# Sheet1.net
KiCad netlist of a schematic drawn in Altium Designer
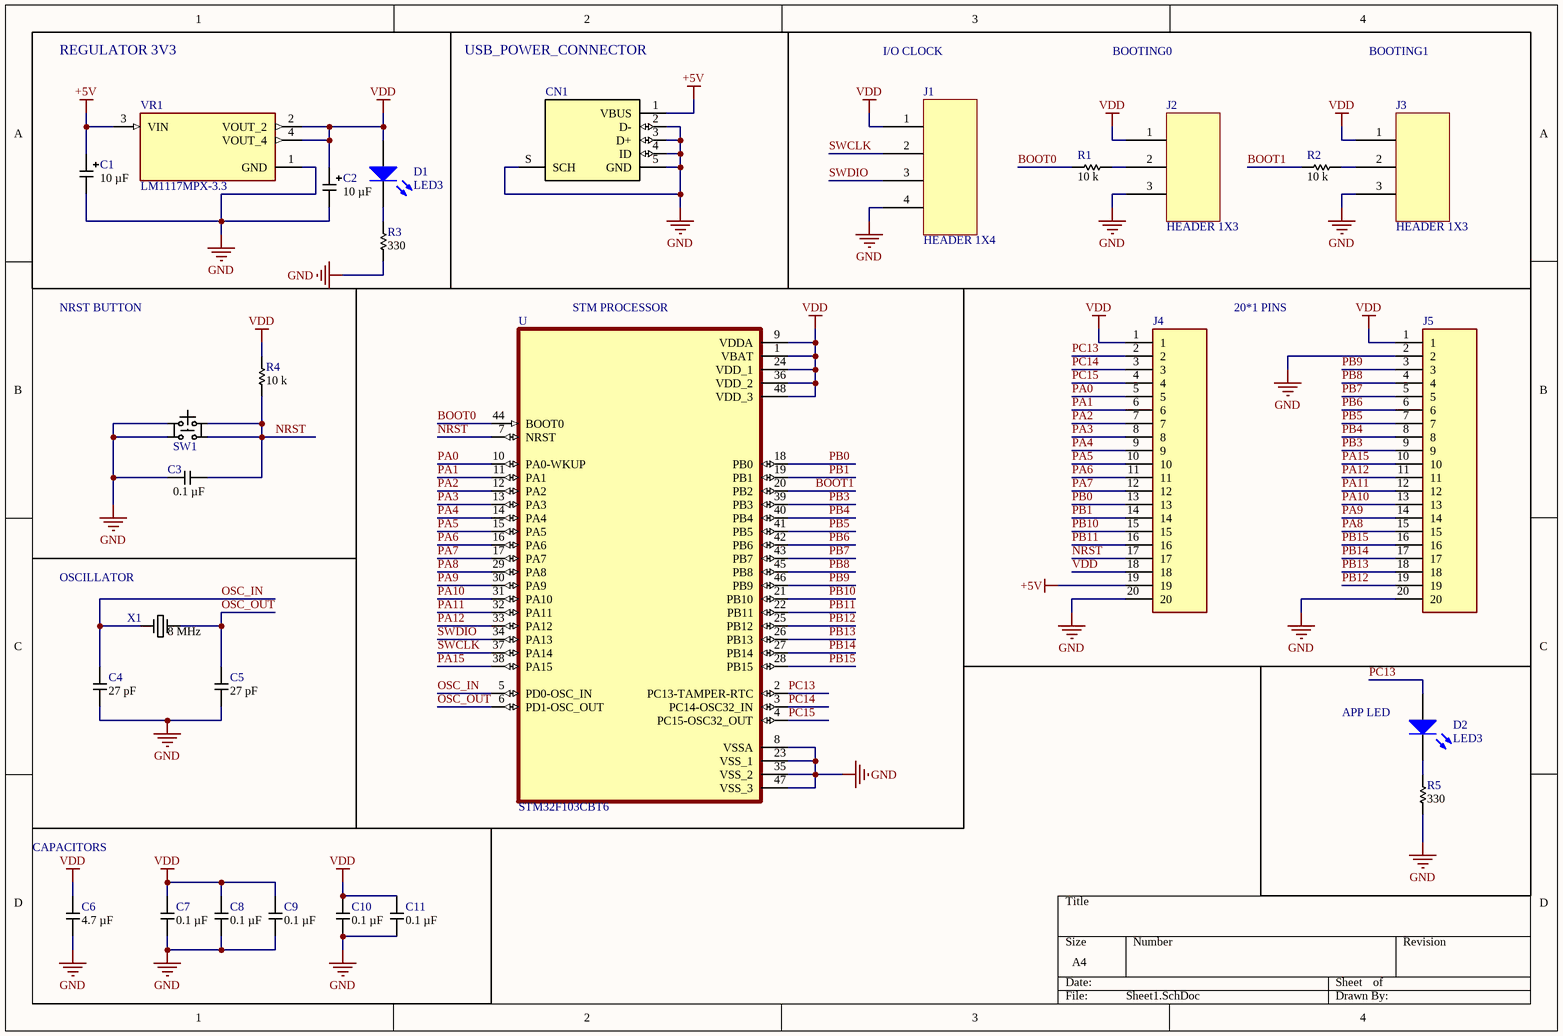
[diagram p0: Sheet1.SchDoc]

(export (version "E")
  (design (tool "Eeschema 10.0.6"))
  (components
    (comp (ref "C1")
      (value "T495B106K025ATE750")
      (footprint "KEMET_CAP_TAN-B")
      (description "CAP TANT 10UF 10% 25V 1411")
      (fields (field (name "CAPACITANCE") "10 µF"))
      (libsource (lib "Tantalum Capacitors") (part "T495B106K025ATE750"))
    )
    (comp (ref "C2")
      (value "T495B106K025ATE750")
      (footprint "KEMET_CAP_TAN-B")
      (description "CAP TANT 10UF 10% 25V 1411")
      (fields (field (name "CAPACITANCE") "10 µF"))
      (libsource (lib "Tantalum Capacitors") (part "T495B106K025ATE750"))
    )
    (comp (ref "C3")
      (value "CL10B104KB8NNNC")
      (footprint "SAMSUNG_CAP_0603_090")
      (description "CAP CER 0.1UF 50V X7R 0603")
      (fields (field (name "CAPACITANCE") "0.1 µF"))
      (libsource (lib "Ceramic Capacitors") (part "CL10B104KB8NNNC"))
    )
    (comp (ref "C4")
      (value "CL21C270JBANNNC")
      (footprint "SAMSUNG_CAP_0805_075")
      (description "CAP CER 27PF 50V C0G/NP0 0805")
      (fields (field (name "CAPACITANCE") "27 pF"))
      (libsource (lib "Ceramic Capacitors") (part "CL21C270JBANNNC"))
    )
    (comp (ref "C5")
      (value "CL21C270JBANNNC")
      (footprint "SAMSUNG_CAP_0805_075")
      (description "CAP CER 27PF 50V C0G/NP0 0805")
      (fields (field (name "CAPACITANCE") "27 pF"))
      (libsource (lib "Ceramic Capacitors") (part "CL21C270JBANNNC"))
    )
    (comp (ref "C6")
      (value "CL21A475KACLRNC")
      (footprint "SAMSUNG_CAP_0805_095")
      (description "CAP CER 4.7UF 25V X5R 0805")
      (fields (field (name "CAPACITANCE") "4.7 µF"))
      (libsource (lib "Ceramic Capacitors") (part "CL21A475KACLRNC"))
    )
    (comp (ref "C7")
      (value "CL21B104MACNNNC")
      (footprint "SAMSUNG_CAP_0805_095")
      (description "CAP CER 0.1UF 25V X7R 0805")
      (fields (field (name "CAPACITANCE") "0.1 µF"))
      (libsource (lib "Ceramic Capacitors") (part "CL21B104MACNNNC"))
    )
    (comp (ref "C8")
      (value "CL21B104MACNNNC")
      (footprint "SAMSUNG_CAP_0805_095")
      (description "CAP CER 0.1UF 25V X7R 0805")
      (fields (field (name "CAPACITANCE") "0.1 µF"))
      (libsource (lib "Ceramic Capacitors") (part "CL21B104MACNNNC"))
    )
    (comp (ref "C9")
      (value "CL21B104MACNNNC")
      (footprint "SAMSUNG_CAP_0805_095")
      (description "CAP CER 0.1UF 25V X7R 0805")
      (fields (field (name "CAPACITANCE") "0.1 µF"))
      (libsource (lib "Ceramic Capacitors") (part "CL21B104MACNNNC"))
    )
    (comp (ref "C10")
      (value "CL21B104MACNNNC")
      (footprint "SAMSUNG_CAP_0805_095")
      (description "CAP CER 0.1UF 25V X7R 0805")
      (fields (field (name "CAPACITANCE") "0.1 µF"))
      (libsource (lib "Ceramic Capacitors") (part "CL21B104MACNNNC"))
    )
    (comp (ref "C11")
      (value "CL21B104MACNNNC")
      (footprint "SAMSUNG_CAP_0805_095")
      (description "CAP CER 0.1UF 25V X7R 0805")
      (fields (field (name "CAPACITANCE") "0.1 µF"))
      (libsource (lib "Ceramic Capacitors") (part "CL21B104MACNNNC"))
    )
    (comp (ref "CN1")
      (value "5UR2M01MF-105G0BUHM1")
      (footprint "AMTEK_5UR2M01MF-105G0BUHM1")
      (description "CONN RCPT MICRO USB AB 5P SMD RA")
      (libsource (lib "USB, DVI, HDMI Connectors") (part "5UR2M01MF-105G0BUHM1"))
    )
    (comp (ref "D1")
      (value "LED3")
      (footprint "3.5X2.8X1.9")
      (description "Typical BLUE SiC LED")
      (fields (field (name "PUBLISHER") "Altium Limited"))
      (libsource (lib "Miscellaneous Devices") (part "LED3"))
    )
    (comp (ref "D2")
      (value "LED3")
      (footprint "3.5X2.8X1.9")
      (description "Typical BLUE SiC LED")
      (fields (field (name "PUBLISHER") "Altium Limited"))
      (libsource (lib "Miscellaneous Devices") (part "LED3"))
    )
    (comp (ref "J1")
      (value "HEADER 1X4")
      (footprint "HEADER 1X4_2.54mm")
      (libsource (lib "Sch1-schlib") (part "HEADER 1X4"))
    )
    (comp (ref "J2")
      (value "HEADER 1X3")
      (footprint "HEADER 1X3_2.54")
      (libsource (lib "Sch1-schlib") (part "HEADER 1X3"))
    )
    (comp (ref "J3")
      (value "HEADER 1X3")
      (footprint "HEADER 1X3_2.54")
      (libsource (lib "Sch1-schlib") (part "HEADER 1X3"))
    )
    (comp (ref "J4") (value "~") (footprint "20*1 pin") (libsource (lib "Schlib1") (part "20 pin header")))
    (comp (ref "J5") (value "~") (footprint "20*1 pin") (libsource (lib "Schlib1") (part "20 pin header")))
    (comp (ref "R1")
      (value "0603SAJ0103T5E")
      (footprint "ROYALOHM_RES_0603")
      (description "RES SMD 10K OHM 5% 1/10W 0603")
      (fields (field (name "RESISTANCE") "10 k"))
      (libsource (lib "Chip Resistor - Surface Mount") (part "0603SAJ0103T5E"))
    )
    (comp (ref "R2")
      (value "0603SAJ0103T5E")
      (footprint "ROYALOHM_RES_0603")
      (description "RES SMD 10K OHM 5% 1/10W 0603")
      (fields (field (name "RESISTANCE") "10 k"))
      (libsource (lib "Chip Resistor - Surface Mount") (part "0603SAJ0103T5E"))
    )
    (comp (ref "R3")
      (value "0603SAJ0331T5E")
      (footprint "ROYALOHM_RES_0603")
      (description "RES SMD 330R OHM 5% 1/10W 0603")
      (fields (field (name "RESISTANCE") "330"))
      (libsource (lib "Chip Resistor - Surface Mount") (part "0603SAJ0331T5E"))
    )
    (comp (ref "R4")
      (value "0603SAJ0103T5E")
      (footprint "ROYALOHM_RES_0603")
      (description "RES SMD 10K OHM 5% 1/10W 0603")
      (fields (field (name "RESISTANCE") "10 k"))
      (libsource (lib "Chip Resistor - Surface Mount") (part "0603SAJ0103T5E"))
    )
    (comp (ref "R5")
      (value "0603SAJ0331T5E")
      (footprint "ROYALOHM_RES_0603")
      (description "RES SMD 330R OHM 5% 1/10W 0603")
      (fields (field (name "RESISTANCE") "330"))
      (libsource (lib "Chip Resistor - Surface Mount") (part "0603SAJ0331T5E"))
    )
    (comp (ref "SW1")
      (value "434331045822")
      (footprint "WURTH_434331045822")
      (description "SWITCH TACTILE SPST-NO 0.05A 12V")
      (libsource (lib "Tactile Switches") (part "434331045822"))
    )
    (comp (ref "U")
      (value "STM32F103CBT6")
      (footprint "QFP50P900X900X160-48N")
      (description "ARMÂ® CortexÂ®-M3 STM32F1 Microcontroller IC 32-Bit 72MHz 128KB _128K x 8_ FLASH")
      (fields (field (name "MF") "STMicroelectronics"))
      (libsource (lib "SnapEDAsch") (part "STM32F103CBT6"))
    )
    (comp (ref "VR1")
      (value "LM1117MPX-3.3")
      (footprint "VREG_LM1117MPX-3.3")
      (description "800-mA 15-V linear voltage regulator")
      (fields (field (name "MF") "Texas Instruments"))
      (libsource (lib "LM1117MPX-3.3") (part "LM1117MPX-3.3"))
    )
    (comp (ref "X1")
      (value "ABM7-8.000MHZ-D2Y-T")
      (footprint "ABRACON_ABM7")
      (description "CRYSTAL 8.0000MHZ 18PF SMD")
      (fields (field (name "FREQUENCY") "8 MHz"))
      (libsource (lib "Crystals") (part "ABM7-8.000MHZ-D2Y-T"))
    )
  )
  (nets
    (net (code "1") (name "+5V") (class "Default")
      (node (ref "C1") (pin "1") (pinfunction "1_1") (pintype "passive"))
      (node (ref "CN1") (pin "1") (pinfunction "VBUS_1") (pintype "passive"))
      (node (ref "J4") (pin "19") (pinfunction "19_19") (pintype "passive"))
      (node (ref "VR1") (pin "3") (pinfunction "VIN_3") (pintype "input"))
    )
    (net (code "2") (name "/BOOT0") (class "Default")
      (node (ref "R1") (pin "1") (pinfunction "1_1") (pintype "passive"))
      (node (ref "U") (pin "44") (pinfunction "BOOT0_44") (pintype "input"))
    )
    (net (code "3") (name "/BOOT1") (class "Default")
      (node (ref "R2") (pin "1") (pinfunction "1_1") (pintype "passive"))
      (node (ref "U") (pin "20") (pinfunction "PB2_20") (pintype "bidirectional"))
    )
    (net (code "4") (name "/NRST") (class "Default")
      (node (ref "C3") (pin "2") (pinfunction "2_2") (pintype "passive"))
      (node (ref "J4") (pin "17") (pinfunction "17_17") (pintype "passive"))
      (node (ref "R4") (pin "1") (pinfunction "1_1") (pintype "passive"))
      (node (ref "SW1") (pin "2") (pinfunction "2_2") (pintype "passive"))
      (node (ref "SW1") (pin "4") (pinfunction "4_4") (pintype "passive"))
      (node (ref "U") (pin "7") (pinfunction "NRST_7") (pintype "bidirectional"))
    )
    (net (code "5") (name "/OSC_IN") (class "Default")
      (node (ref "C4") (pin "2") (pinfunction "2_2") (pintype "passive"))
      (node (ref "U") (pin "5") (pinfunction "PD0-OSC_IN_5") (pintype "bidirectional"))
      (node (ref "X1") (pin "1") (pinfunction "1_1") (pintype "passive"))
    )
    (net (code "6") (name "/OSC_OUT") (class "Default")
      (node (ref "C5") (pin "2") (pinfunction "2_2") (pintype "passive"))
      (node (ref "U") (pin "6") (pinfunction "PD1-OSC_OUT_6") (pintype "bidirectional"))
      (node (ref "X1") (pin "2") (pinfunction "2_2") (pintype "passive"))
    )
    (net (code "7") (name "/PA0") (class "Default")
      (node (ref "J4") (pin "5") (pinfunction "5_5") (pintype "passive"))
      (node (ref "U") (pin "10") (pinfunction "PA0-WKUP_10") (pintype "bidirectional"))
    )
    (net (code "8") (name "/PA1") (class "Default")
      (node (ref "J4") (pin "6") (pinfunction "6_6") (pintype "passive"))
      (node (ref "U") (pin "11") (pinfunction "PA1_11") (pintype "bidirectional"))
    )
    (net (code "9") (name "/PA2") (class "Default")
      (node (ref "J4") (pin "7") (pinfunction "7_7") (pintype "passive"))
      (node (ref "U") (pin "12") (pinfunction "PA2_12") (pintype "bidirectional"))
    )
    (net (code "10") (name "/PA3") (class "Default")
      (node (ref "J4") (pin "8") (pinfunction "8_8") (pintype "passive"))
      (node (ref "U") (pin "13") (pinfunction "PA3_13") (pintype "bidirectional"))
    )
    (net (code "11") (name "/PA4") (class "Default")
      (node (ref "J4") (pin "9") (pinfunction "9_9") (pintype "passive"))
      (node (ref "U") (pin "14") (pinfunction "PA4_14") (pintype "bidirectional"))
    )
    (net (code "12") (name "/PA5") (class "Default")
      (node (ref "J4") (pin "10") (pinfunction "10_10") (pintype "passive"))
      (node (ref "U") (pin "15") (pinfunction "PA5_15") (pintype "bidirectional"))
    )
    (net (code "13") (name "/PA6") (class "Default")
      (node (ref "J4") (pin "11") (pinfunction "11_11") (pintype "passive"))
      (node (ref "U") (pin "16") (pinfunction "PA6_16") (pintype "bidirectional"))
    )
    (net (code "14") (name "/PA7") (class "Default")
      (node (ref "J4") (pin "12") (pinfunction "12_12") (pintype "passive"))
      (node (ref "U") (pin "17") (pinfunction "PA7_17") (pintype "bidirectional"))
    )
    (net (code "15") (name "/PA8") (class "Default")
      (node (ref "J5") (pin "15") (pinfunction "15_15") (pintype "passive"))
      (node (ref "U") (pin "29") (pinfunction "PA8_29") (pintype "bidirectional"))
    )
    (net (code "16") (name "/PA9") (class "Default")
      (node (ref "J5") (pin "14") (pinfunction "14_14") (pintype "passive"))
      (node (ref "U") (pin "30") (pinfunction "PA9_30") (pintype "bidirectional"))
    )
    (net (code "17") (name "/PA10") (class "Default")
      (node (ref "J5") (pin "13") (pinfunction "13_13") (pintype "passive"))
      (node (ref "U") (pin "31") (pinfunction "PA10_31") (pintype "bidirectional"))
    )
    (net (code "18") (name "/PA11") (class "Default")
      (node (ref "J5") (pin "12") (pinfunction "12_12") (pintype "passive"))
      (node (ref "U") (pin "32") (pinfunction "PA11_32") (pintype "bidirectional"))
    )
    (net (code "19") (name "/PA12") (class "Default")
      (node (ref "J5") (pin "11") (pinfunction "11_11") (pintype "passive"))
      (node (ref "U") (pin "33") (pinfunction "PA12_33") (pintype "bidirectional"))
    )
    (net (code "20") (name "/PA15") (class "Default")
      (node (ref "J5") (pin "10") (pinfunction "10_10") (pintype "passive"))
      (node (ref "U") (pin "38") (pinfunction "PA15_38") (pintype "bidirectional"))
    )
    (net (code "21") (name "/PB0") (class "Default")
      (node (ref "J4") (pin "13") (pinfunction "13_13") (pintype "passive"))
      (node (ref "U") (pin "18") (pinfunction "PB0_18") (pintype "bidirectional"))
    )
    (net (code "22") (name "/PB1") (class "Default")
      (node (ref "J4") (pin "14") (pinfunction "14_14") (pintype "passive"))
      (node (ref "U") (pin "19") (pinfunction "PB1_19") (pintype "bidirectional"))
    )
    (net (code "23") (name "/PB3") (class "Default")
      (node (ref "J5") (pin "9") (pinfunction "9_9") (pintype "passive"))
      (node (ref "U") (pin "39") (pinfunction "PB3_39") (pintype "bidirectional"))
    )
    (net (code "24") (name "/PB4") (class "Default")
      (node (ref "J5") (pin "8") (pinfunction "8_8") (pintype "passive"))
      (node (ref "U") (pin "40") (pinfunction "PB4_40") (pintype "bidirectional"))
    )
    (net (code "25") (name "/PB5") (class "Default")
      (node (ref "J5") (pin "7") (pinfunction "7_7") (pintype "passive"))
      (node (ref "U") (pin "41") (pinfunction "PB5_41") (pintype "bidirectional"))
    )
    (net (code "26") (name "/PB6") (class "Default")
      (node (ref "J5") (pin "6") (pinfunction "6_6") (pintype "passive"))
      (node (ref "U") (pin "42") (pinfunction "PB6_42") (pintype "bidirectional"))
    )
    (net (code "27") (name "/PB7") (class "Default")
      (node (ref "J5") (pin "5") (pinfunction "5_5") (pintype "passive"))
      (node (ref "U") (pin "43") (pinfunction "PB7_43") (pintype "bidirectional"))
    )
    (net (code "28") (name "/PB8") (class "Default")
      (node (ref "J5") (pin "4") (pinfunction "4_4") (pintype "passive"))
      (node (ref "U") (pin "45") (pinfunction "PB8_45") (pintype "bidirectional"))
    )
    (net (code "29") (name "/PB9") (class "Default")
      (node (ref "J5") (pin "3") (pinfunction "3_3") (pintype "passive"))
      (node (ref "U") (pin "46") (pinfunction "PB9_46") (pintype "bidirectional"))
    )
    (net (code "30") (name "/PB10") (class "Default")
      (node (ref "J4") (pin "15") (pinfunction "15_15") (pintype "passive"))
      (node (ref "U") (pin "21") (pinfunction "PB10_21") (pintype "bidirectional"))
    )
    (net (code "31") (name "/PB11") (class "Default")
      (node (ref "J4") (pin "16") (pinfunction "16_16") (pintype "passive"))
      (node (ref "U") (pin "22") (pinfunction "PB11_22") (pintype "bidirectional"))
    )
    (net (code "32") (name "/PB12") (class "Default")
      (node (ref "J5") (pin "19") (pinfunction "19_19") (pintype "passive"))
      (node (ref "U") (pin "25") (pinfunction "PB12_25") (pintype "bidirectional"))
    )
    (net (code "33") (name "/PB13") (class "Default")
      (node (ref "J5") (pin "18") (pinfunction "18_18") (pintype "passive"))
      (node (ref "U") (pin "26") (pinfunction "PB13_26") (pintype "bidirectional"))
    )
    (net (code "34") (name "/PB14") (class "Default")
      (node (ref "J5") (pin "17") (pinfunction "17_17") (pintype "passive"))
      (node (ref "U") (pin "27") (pinfunction "PB14_27") (pintype "bidirectional"))
    )
    (net (code "35") (name "/PB15") (class "Default")
      (node (ref "J5") (pin "16") (pinfunction "16_16") (pintype "passive"))
      (node (ref "U") (pin "28") (pinfunction "PB15_28") (pintype "bidirectional"))
    )
    (net (code "36") (name "/PC13") (class "Default")
      (node (ref "D2") (pin "1") (pinfunction "A_1") (pintype "passive"))
      (node (ref "J4") (pin "2") (pinfunction "2_2") (pintype "passive"))
      (node (ref "U") (pin "2") (pinfunction "PC13-TAMPER-RTC_2") (pintype "bidirectional"))
    )
    (net (code "37") (name "/PC14") (class "Default")
      (node (ref "J4") (pin "3") (pinfunction "3_3") (pintype "passive"))
      (node (ref "U") (pin "3") (pinfunction "PC14-OSC32_IN_3") (pintype "bidirectional"))
    )
    (net (code "38") (name "/PC15") (class "Default")
      (node (ref "J4") (pin "4") (pinfunction "4_4") (pintype "passive"))
      (node (ref "U") (pin "4") (pinfunction "PC15-OSC32_OUT_4") (pintype "bidirectional"))
    )
    (net (code "39") (name "/SWCLK") (class "Default")
      (node (ref "J1") (pin "2") (pintype "passive"))
      (node (ref "U") (pin "37") (pinfunction "PA14_37") (pintype "bidirectional"))
    )
    (net (code "40") (name "/SWDIO") (class "Default")
      (node (ref "J1") (pin "3") (pintype "passive"))
      (node (ref "U") (pin "34") (pinfunction "PA13_34") (pintype "bidirectional"))
    )
    (net (code "41") (name "GND") (class "Default")
      (node (ref "C1") (pin "2") (pinfunction "2_2") (pintype "passive"))
      (node (ref "C10") (pin "1") (pinfunction "1_1") (pintype "passive"))
      (node (ref "C11") (pin "1") (pinfunction "1_1") (pintype "passive"))
      (node (ref "C2") (pin "2") (pinfunction "2_2") (pintype "passive"))
      (node (ref "C3") (pin "1") (pinfunction "1_1") (pintype "passive"))
      (node (ref "C4") (pin "1") (pinfunction "1_1") (pintype "passive"))
      (node (ref "C5") (pin "1") (pinfunction "1_1") (pintype "passive"))
      (node (ref "C6") (pin "1") (pinfunction "1_1") (pintype "passive"))
      (node (ref "C7") (pin "1") (pinfunction "1_1") (pintype "passive"))
      (node (ref "C8") (pin "1") (pinfunction "1_1") (pintype "passive"))
      (node (ref "C9") (pin "1") (pinfunction "1_1") (pintype "passive"))
      (node (ref "CN1") (pin "2") (pinfunction "D-_2") (pintype "bidirectional"))
      (node (ref "CN1") (pin "3") (pinfunction "D+_3") (pintype "bidirectional"))
      (node (ref "CN1") (pin "4") (pinfunction "ID_4") (pintype "bidirectional"))
      (node (ref "CN1") (pin "5") (pinfunction "GND_5") (pintype "passive"))
      (node (ref "CN1") (pin "S") (pinfunction "SCH_S") (pintype "passive"))
      (node (ref "J1") (pin "4") (pintype "passive"))
      (node (ref "J2") (pin "3") (pintype "passive"))
      (node (ref "J3") (pin "3") (pintype "passive"))
      (node (ref "J4") (pin "20") (pinfunction "20_20") (pintype "passive"))
      (node (ref "J5") (pin "2") (pinfunction "2_2") (pintype "passive"))
      (node (ref "J5") (pin "20") (pinfunction "20_20") (pintype "passive"))
      (node (ref "R3") (pin "1") (pinfunction "1_1") (pintype "passive"))
      (node (ref "R5") (pin "1") (pinfunction "1_1") (pintype "passive"))
      (node (ref "SW1") (pin "1") (pinfunction "1_1") (pintype "passive"))
      (node (ref "SW1") (pin "3") (pinfunction "3_3") (pintype "passive"))
      (node (ref "U") (pin "23") (pinfunction "VSS_1_23") (pintype "power_in"))
      (node (ref "U") (pin "35") (pinfunction "VSS_2_35") (pintype "power_in"))
      (node (ref "U") (pin "47") (pinfunction "VSS_3_47") (pintype "power_in"))
      (node (ref "U") (pin "8") (pinfunction "VSSA_8") (pintype "power_in"))
      (node (ref "VR1") (pin "1") (pinfunction "GND_1") (pintype "power_in"))
    )
    (net (code "42") (name "Net-(D1-K)") (class "Default")
      (node (ref "D1") (pin "2") (pinfunction "K_2") (pintype "passive"))
      (node (ref "R3") (pin "2") (pinfunction "2_2") (pintype "passive"))
    )
    (net (code "43") (name "Net-(D2-K)") (class "Default")
      (node (ref "D2") (pin "2") (pinfunction "K_2") (pintype "passive"))
      (node (ref "R5") (pin "2") (pinfunction "2_2") (pintype "passive"))
    )
    (net (code "44") (name "Net-(J2-Pad2)") (class "Default")
      (node (ref "J2") (pin "2") (pintype "passive"))
      (node (ref "R1") (pin "2") (pinfunction "2_2") (pintype "passive"))
    )
    (net (code "45") (name "Net-(J3-Pad2)") (class "Default")
      (node (ref "J3") (pin "2") (pintype "passive"))
      (node (ref "R2") (pin "2") (pinfunction "2_2") (pintype "passive"))
    )
    (net (code "46") (name "VDD") (class "Default")
      (node (ref "C10") (pin "2") (pinfunction "2_2") (pintype "passive"))
      (node (ref "C11") (pin "2") (pinfunction "2_2") (pintype "passive"))
      (node (ref "C2") (pin "1") (pinfunction "1_1") (pintype "passive"))
      (node (ref "C6") (pin "2") (pinfunction "2_2") (pintype "passive"))
      (node (ref "C7") (pin "2") (pinfunction "2_2") (pintype "passive"))
      (node (ref "C8") (pin "2") (pinfunction "2_2") (pintype "passive"))
      (node (ref "C9") (pin "2") (pinfunction "2_2") (pintype "passive"))
      (node (ref "D1") (pin "1") (pinfunction "A_1") (pintype "passive"))
      (node (ref "J1") (pin "1") (pintype "passive"))
      (node (ref "J2") (pin "1") (pintype "passive"))
      (node (ref "J3") (pin "1") (pintype "passive"))
      (node (ref "J4") (pin "1") (pinfunction "1_1") (pintype "passive"))
      (node (ref "J4") (pin "18") (pinfunction "18_18") (pintype "passive"))
      (node (ref "J5") (pin "1") (pinfunction "1_1") (pintype "passive"))
      (node (ref "R4") (pin "2") (pinfunction "2_2") (pintype "passive"))
      (node (ref "U") (pin "1") (pinfunction "VBAT_1") (pintype "power_in"))
      (node (ref "U") (pin "24") (pinfunction "VDD_1_24") (pintype "power_in"))
      (node (ref "U") (pin "36") (pinfunction "VDD_2_36") (pintype "power_in"))
      (node (ref "U") (pin "48") (pinfunction "VDD_3_48") (pintype "power_in"))
      (node (ref "U") (pin "9") (pinfunction "VDDA_9") (pintype "power_in"))
      (node (ref "VR1") (pin "2") (pinfunction "VOUT_2_2") (pintype "output"))
      (node (ref "VR1") (pin "4") (pinfunction "VOUT_4_4") (pintype "output"))
    )
  )
)
